# HPCC_Connector_A.net
KiCad netlist of a schematic drawn in Altium Designer
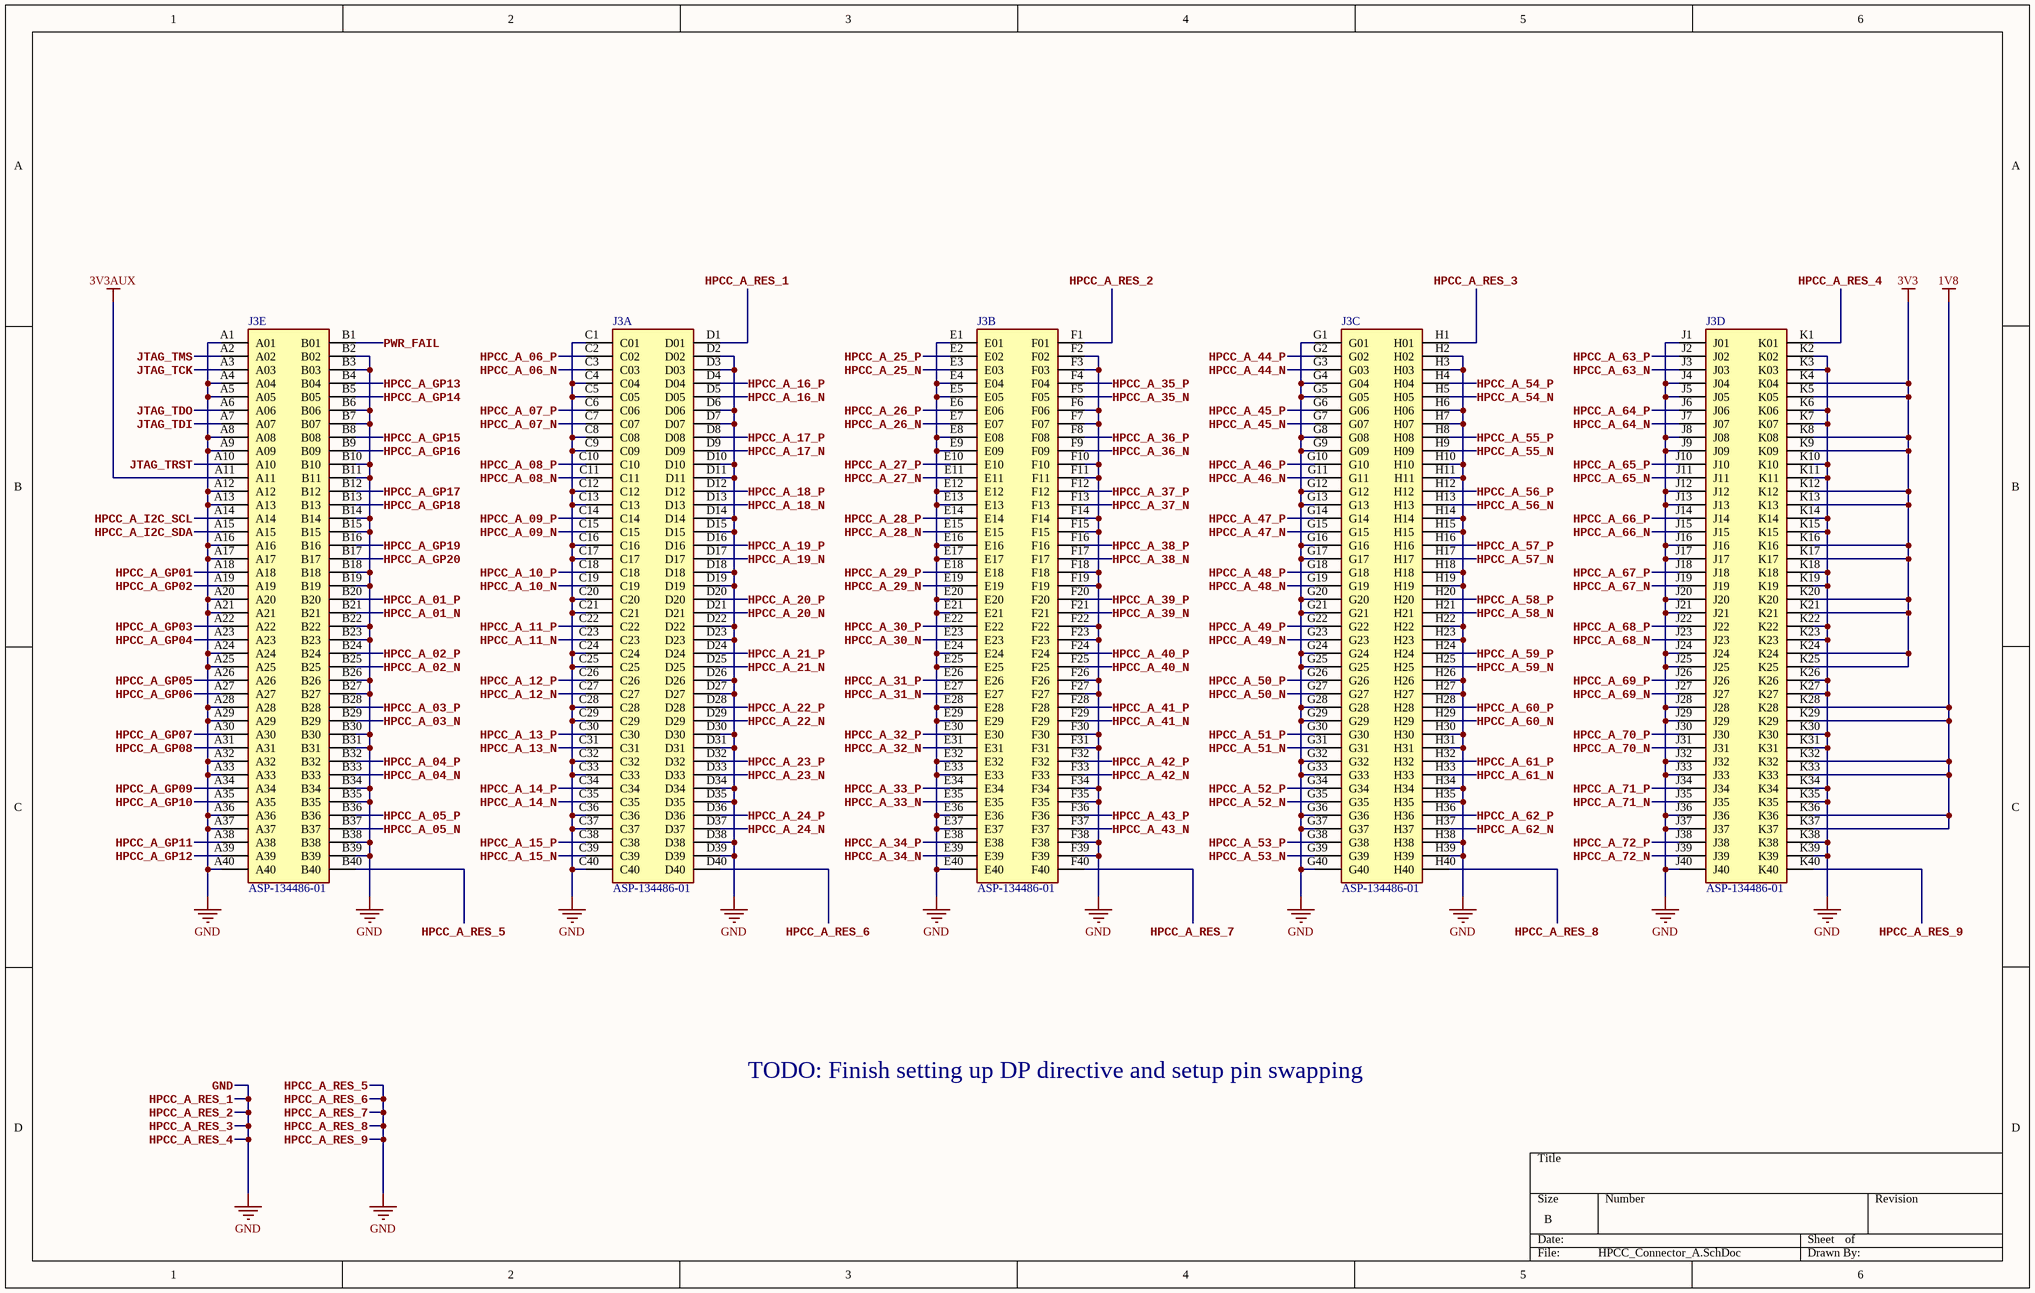
[diagram p0: HPCC_Connector_A.SchDoc]

(export (version "E")
  (design (tool "Eeschema 10.0.6"))
  (components
    (comp (ref "J3")
      (value "ASP-134486-01")
      (footprint "SAMTEC_ASP-134486-01")
      (description "400 Position Connector Array, Female Sockets Surface Mount Gold")
      (fields (field (name "MANUFACTURER") "Samtec"))
      (libsource (lib "Capstone_Schematic_Library") (part "ASP-134486-01"))
    )
  )
  (nets
    (net (code "1") (name "/HPCC_A_01_N") (class "Default")
      (node (ref "J3") (pin "B21") (pinfunction "B21_B21") (pintype "passive"))
    )
    (net (code "2") (name "/HPCC_A_01_P") (class "Default")
      (node (ref "J3") (pin "B20") (pinfunction "B20_B20") (pintype "passive"))
    )
    (net (code "3") (name "/HPCC_A_02_N") (class "Default")
      (node (ref "J3") (pin "B25") (pinfunction "B25_B25") (pintype "passive"))
    )
    (net (code "4") (name "/HPCC_A_02_P") (class "Default")
      (node (ref "J3") (pin "B24") (pinfunction "B24_B24") (pintype "passive"))
    )
    (net (code "5") (name "/HPCC_A_03_N") (class "Default")
      (node (ref "J3") (pin "B29") (pinfunction "B29_B29") (pintype "passive"))
    )
    (net (code "6") (name "/HPCC_A_03_P") (class "Default")
      (node (ref "J3") (pin "B28") (pinfunction "B28_B28") (pintype "passive"))
    )
    (net (code "7") (name "/HPCC_A_04_N") (class "Default")
      (node (ref "J3") (pin "B33") (pinfunction "B33_B33") (pintype "passive"))
    )
    (net (code "8") (name "/HPCC_A_04_P") (class "Default")
      (node (ref "J3") (pin "B32") (pinfunction "B32_B32") (pintype "passive"))
    )
    (net (code "9") (name "/HPCC_A_05_N") (class "Default")
      (node (ref "J3") (pin "B37") (pinfunction "B37_B37") (pintype "passive"))
    )
    (net (code "10") (name "/HPCC_A_05_P") (class "Default")
      (node (ref "J3") (pin "B36") (pinfunction "B36_B36") (pintype "passive"))
    )
    (net (code "11") (name "/HPCC_A_06_N") (class "Default")
      (node (ref "J3") (pin "C3") (pinfunction "C03_C3") (pintype "passive"))
    )
    (net (code "12") (name "/HPCC_A_06_P") (class "Default")
      (node (ref "J3") (pin "C2") (pinfunction "C02_C2") (pintype "passive"))
    )
    (net (code "13") (name "/HPCC_A_07_N") (class "Default")
      (node (ref "J3") (pin "C7") (pinfunction "C07_C7") (pintype "passive"))
    )
    (net (code "14") (name "/HPCC_A_07_P") (class "Default")
      (node (ref "J3") (pin "C6") (pinfunction "C06_C6") (pintype "passive"))
    )
    (net (code "15") (name "/HPCC_A_08_N") (class "Default")
      (node (ref "J3") (pin "C11") (pinfunction "C11_C11") (pintype "passive"))
    )
    (net (code "16") (name "/HPCC_A_08_P") (class "Default")
      (node (ref "J3") (pin "C10") (pinfunction "C10_C10") (pintype "passive"))
    )
    (net (code "17") (name "/HPCC_A_09_N") (class "Default")
      (node (ref "J3") (pin "C15") (pinfunction "C15_C15") (pintype "passive"))
    )
    (net (code "18") (name "/HPCC_A_09_P") (class "Default")
      (node (ref "J3") (pin "C14") (pinfunction "C14_C14") (pintype "passive"))
    )
    (net (code "19") (name "/HPCC_A_10_N") (class "Default")
      (node (ref "J3") (pin "C19") (pinfunction "C19_C19") (pintype "passive"))
    )
    (net (code "20") (name "/HPCC_A_10_P") (class "Default")
      (node (ref "J3") (pin "C18") (pinfunction "C18_C18") (pintype "passive"))
    )
    (net (code "21") (name "/HPCC_A_11_N") (class "Default")
      (node (ref "J3") (pin "C23") (pinfunction "C23_C23") (pintype "passive"))
    )
    (net (code "22") (name "/HPCC_A_11_P") (class "Default")
      (node (ref "J3") (pin "C22") (pinfunction "C22_C22") (pintype "passive"))
    )
    (net (code "23") (name "/HPCC_A_12_N") (class "Default")
      (node (ref "J3") (pin "C27") (pinfunction "C27_C27") (pintype "passive"))
    )
    (net (code "24") (name "/HPCC_A_12_P") (class "Default")
      (node (ref "J3") (pin "C26") (pinfunction "C26_C26") (pintype "passive"))
    )
    (net (code "25") (name "/HPCC_A_13_N") (class "Default")
      (node (ref "J3") (pin "C31") (pinfunction "C31_C31") (pintype "passive"))
    )
    (net (code "26") (name "/HPCC_A_13_P") (class "Default")
      (node (ref "J3") (pin "C30") (pinfunction "C30_C30") (pintype "passive"))
    )
    (net (code "27") (name "/HPCC_A_14_N") (class "Default")
      (node (ref "J3") (pin "C35") (pinfunction "C35_C35") (pintype "passive"))
    )
    (net (code "28") (name "/HPCC_A_14_P") (class "Default")
      (node (ref "J3") (pin "C34") (pinfunction "C34_C34") (pintype "passive"))
    )
    (net (code "29") (name "/HPCC_A_15_N") (class "Default")
      (node (ref "J3") (pin "C39") (pinfunction "C39_C39") (pintype "passive"))
    )
    (net (code "30") (name "/HPCC_A_15_P") (class "Default")
      (node (ref "J3") (pin "C38") (pinfunction "C38_C38") (pintype "passive"))
    )
    (net (code "31") (name "/HPCC_A_16_N") (class "Default")
      (node (ref "J3") (pin "D5") (pinfunction "D05_D5") (pintype "passive"))
    )
    (net (code "32") (name "/HPCC_A_16_P") (class "Default")
      (node (ref "J3") (pin "D4") (pinfunction "D04_D4") (pintype "passive"))
    )
    (net (code "33") (name "/HPCC_A_17_N") (class "Default")
      (node (ref "J3") (pin "D9") (pinfunction "D09_D9") (pintype "passive"))
    )
    (net (code "34") (name "/HPCC_A_17_P") (class "Default")
      (node (ref "J3") (pin "D8") (pinfunction "D08_D8") (pintype "passive"))
    )
    (net (code "35") (name "/HPCC_A_18_N") (class "Default")
      (node (ref "J3") (pin "D13") (pinfunction "D13_D13") (pintype "passive"))
    )
    (net (code "36") (name "/HPCC_A_18_P") (class "Default")
      (node (ref "J3") (pin "D12") (pinfunction "D12_D12") (pintype "passive"))
    )
    (net (code "37") (name "/HPCC_A_19_N") (class "Default")
      (node (ref "J3") (pin "D17") (pinfunction "D17_D17") (pintype "passive"))
    )
    (net (code "38") (name "/HPCC_A_19_P") (class "Default")
      (node (ref "J3") (pin "D16") (pinfunction "D16_D16") (pintype "passive"))
    )
    (net (code "39") (name "/HPCC_A_20_N") (class "Default")
      (node (ref "J3") (pin "D21") (pinfunction "D21_D21") (pintype "passive"))
    )
    (net (code "40") (name "/HPCC_A_20_P") (class "Default")
      (node (ref "J3") (pin "D20") (pinfunction "D20_D20") (pintype "passive"))
    )
    (net (code "41") (name "/HPCC_A_21_N") (class "Default")
      (node (ref "J3") (pin "D25") (pinfunction "D25_D25") (pintype "passive"))
    )
    (net (code "42") (name "/HPCC_A_21_P") (class "Default")
      (node (ref "J3") (pin "D24") (pinfunction "D24_D24") (pintype "passive"))
    )
    (net (code "43") (name "/HPCC_A_22_N") (class "Default")
      (node (ref "J3") (pin "D29") (pinfunction "D29_D29") (pintype "passive"))
    )
    (net (code "44") (name "/HPCC_A_22_P") (class "Default")
      (node (ref "J3") (pin "D28") (pinfunction "D28_D28") (pintype "passive"))
    )
    (net (code "45") (name "/HPCC_A_23_N") (class "Default")
      (node (ref "J3") (pin "D33") (pinfunction "D33_D33") (pintype "passive"))
    )
    (net (code "46") (name "/HPCC_A_23_P") (class "Default")
      (node (ref "J3") (pin "D32") (pinfunction "D32_D32") (pintype "passive"))
    )
    (net (code "47") (name "/HPCC_A_24_N") (class "Default")
      (node (ref "J3") (pin "D37") (pinfunction "D37_D37") (pintype "passive"))
    )
    (net (code "48") (name "/HPCC_A_24_P") (class "Default")
      (node (ref "J3") (pin "D36") (pinfunction "D36_D36") (pintype "passive"))
    )
    (net (code "49") (name "/HPCC_A_25_N") (class "Default")
      (node (ref "J3") (pin "E3") (pinfunction "E03_E3") (pintype "passive"))
    )
    (net (code "50") (name "/HPCC_A_25_P") (class "Default")
      (node (ref "J3") (pin "E2") (pinfunction "E02_E2") (pintype "passive"))
    )
    (net (code "51") (name "/HPCC_A_26_N") (class "Default")
      (node (ref "J3") (pin "E7") (pinfunction "E07_E7") (pintype "passive"))
    )
    (net (code "52") (name "/HPCC_A_26_P") (class "Default")
      (node (ref "J3") (pin "E6") (pinfunction "E06_E6") (pintype "passive"))
    )
    (net (code "53") (name "/HPCC_A_27_N") (class "Default")
      (node (ref "J3") (pin "E11") (pinfunction "E11_E11") (pintype "passive"))
    )
    (net (code "54") (name "/HPCC_A_27_P") (class "Default")
      (node (ref "J3") (pin "E10") (pinfunction "E10_E10") (pintype "passive"))
    )
    (net (code "55") (name "/HPCC_A_28_N") (class "Default")
      (node (ref "J3") (pin "E15") (pinfunction "E15_E15") (pintype "passive"))
    )
    (net (code "56") (name "/HPCC_A_28_P") (class "Default")
      (node (ref "J3") (pin "E14") (pinfunction "E14_E14") (pintype "passive"))
    )
    (net (code "57") (name "/HPCC_A_29_N") (class "Default")
      (node (ref "J3") (pin "E19") (pinfunction "E19_E19") (pintype "passive"))
    )
    (net (code "58") (name "/HPCC_A_29_P") (class "Default")
      (node (ref "J3") (pin "E18") (pinfunction "E18_E18") (pintype "passive"))
    )
    (net (code "59") (name "/HPCC_A_30_N") (class "Default")
      (node (ref "J3") (pin "E23") (pinfunction "E23_E23") (pintype "passive"))
    )
    (net (code "60") (name "/HPCC_A_30_P") (class "Default")
      (node (ref "J3") (pin "E22") (pinfunction "E22_E22") (pintype "passive"))
    )
    (net (code "61") (name "/HPCC_A_31_N") (class "Default")
      (node (ref "J3") (pin "E27") (pinfunction "E27_E27") (pintype "passive"))
    )
    (net (code "62") (name "/HPCC_A_31_P") (class "Default")
      (node (ref "J3") (pin "E26") (pinfunction "E26_E26") (pintype "passive"))
    )
    (net (code "63") (name "/HPCC_A_32_N") (class "Default")
      (node (ref "J3") (pin "E31") (pinfunction "E31_E31") (pintype "passive"))
    )
    (net (code "64") (name "/HPCC_A_32_P") (class "Default")
      (node (ref "J3") (pin "E30") (pinfunction "E30_E30") (pintype "passive"))
    )
    (net (code "65") (name "/HPCC_A_33_N") (class "Default")
      (node (ref "J3") (pin "E35") (pinfunction "E35_E35") (pintype "passive"))
    )
    (net (code "66") (name "/HPCC_A_33_P") (class "Default")
      (node (ref "J3") (pin "E34") (pinfunction "E34_E34") (pintype "passive"))
    )
    (net (code "67") (name "/HPCC_A_34_N") (class "Default")
      (node (ref "J3") (pin "E39") (pinfunction "E39_E39") (pintype "passive"))
    )
    (net (code "68") (name "/HPCC_A_34_P") (class "Default")
      (node (ref "J3") (pin "E38") (pinfunction "E38_E38") (pintype "passive"))
    )
    (net (code "69") (name "/HPCC_A_35_N") (class "Default")
      (node (ref "J3") (pin "F5") (pinfunction "F05_F5") (pintype "passive"))
    )
    (net (code "70") (name "/HPCC_A_35_P") (class "Default")
      (node (ref "J3") (pin "F4") (pinfunction "F04_F4") (pintype "passive"))
    )
    (net (code "71") (name "/HPCC_A_36_N") (class "Default")
      (node (ref "J3") (pin "F9") (pinfunction "F09_F9") (pintype "passive"))
    )
    (net (code "72") (name "/HPCC_A_36_P") (class "Default")
      (node (ref "J3") (pin "F8") (pinfunction "F08_F8") (pintype "passive"))
    )
    (net (code "73") (name "/HPCC_A_37_N") (class "Default")
      (node (ref "J3") (pin "F13") (pinfunction "F13_F13") (pintype "passive"))
    )
    (net (code "74") (name "/HPCC_A_37_P") (class "Default")
      (node (ref "J3") (pin "F12") (pinfunction "F12_F12") (pintype "passive"))
    )
    (net (code "75") (name "/HPCC_A_38_N") (class "Default")
      (node (ref "J3") (pin "F17") (pinfunction "F17_F17") (pintype "passive"))
    )
    (net (code "76") (name "/HPCC_A_38_P") (class "Default")
      (node (ref "J3") (pin "F16") (pinfunction "F16_F16") (pintype "passive"))
    )
    (net (code "77") (name "/HPCC_A_39_N") (class "Default")
      (node (ref "J3") (pin "F21") (pinfunction "F21_F21") (pintype "passive"))
    )
    (net (code "78") (name "/HPCC_A_39_P") (class "Default")
      (node (ref "J3") (pin "F20") (pinfunction "F20_F20") (pintype "passive"))
    )
    (net (code "79") (name "/HPCC_A_40_N") (class "Default")
      (node (ref "J3") (pin "F25") (pinfunction "F25_F25") (pintype "passive"))
    )
    (net (code "80") (name "/HPCC_A_40_P") (class "Default")
      (node (ref "J3") (pin "F24") (pinfunction "F24_F24") (pintype "passive"))
    )
    (net (code "81") (name "/HPCC_A_41_N") (class "Default")
      (node (ref "J3") (pin "F29") (pinfunction "F29_F29") (pintype "passive"))
    )
    (net (code "82") (name "/HPCC_A_41_P") (class "Default")
      (node (ref "J3") (pin "F28") (pinfunction "F28_F28") (pintype "passive"))
    )
    (net (code "83") (name "/HPCC_A_42_N") (class "Default")
      (node (ref "J3") (pin "F33") (pinfunction "F33_F33") (pintype "passive"))
    )
    (net (code "84") (name "/HPCC_A_42_P") (class "Default")
      (node (ref "J3") (pin "F32") (pinfunction "F32_F32") (pintype "passive"))
    )
    (net (code "85") (name "/HPCC_A_43_N") (class "Default")
      (node (ref "J3") (pin "F37") (pinfunction "F37_F37") (pintype "passive"))
    )
    (net (code "86") (name "/HPCC_A_43_P") (class "Default")
      (node (ref "J3") (pin "F36") (pinfunction "F36_F36") (pintype "passive"))
    )
    (net (code "87") (name "/HPCC_A_44_N") (class "Default")
      (node (ref "J3") (pin "G3") (pinfunction "G03_G3") (pintype "passive"))
    )
    (net (code "88") (name "/HPCC_A_44_P") (class "Default")
      (node (ref "J3") (pin "G2") (pinfunction "G02_G2") (pintype "passive"))
    )
    (net (code "89") (name "/HPCC_A_45_N") (class "Default")
      (node (ref "J3") (pin "G7") (pinfunction "G07_G7") (pintype "passive"))
    )
    (net (code "90") (name "/HPCC_A_45_P") (class "Default")
      (node (ref "J3") (pin "G6") (pinfunction "G06_G6") (pintype "passive"))
    )
    (net (code "91") (name "/HPCC_A_46_N") (class "Default")
      (node (ref "J3") (pin "G11") (pinfunction "G11_G11") (pintype "passive"))
    )
    (net (code "92") (name "/HPCC_A_46_P") (class "Default")
      (node (ref "J3") (pin "G10") (pinfunction "G10_G10") (pintype "passive"))
    )
    (net (code "93") (name "/HPCC_A_47_N") (class "Default")
      (node (ref "J3") (pin "G15") (pinfunction "G15_G15") (pintype "passive"))
    )
    (net (code "94") (name "/HPCC_A_47_P") (class "Default")
      (node (ref "J3") (pin "G14") (pinfunction "G14_G14") (pintype "passive"))
    )
    (net (code "95") (name "/HPCC_A_48_N") (class "Default")
      (node (ref "J3") (pin "G19") (pinfunction "G19_G19") (pintype "passive"))
    )
    (net (code "96") (name "/HPCC_A_48_P") (class "Default")
      (node (ref "J3") (pin "G18") (pinfunction "G18_G18") (pintype "passive"))
    )
    (net (code "97") (name "/HPCC_A_49_N") (class "Default")
      (node (ref "J3") (pin "G23") (pinfunction "G23_G23") (pintype "passive"))
    )
    (net (code "98") (name "/HPCC_A_49_P") (class "Default")
      (node (ref "J3") (pin "G22") (pinfunction "G22_G22") (pintype "passive"))
    )
    (net (code "99") (name "/HPCC_A_50_N") (class "Default")
      (node (ref "J3") (pin "G27") (pinfunction "G27_G27") (pintype "passive"))
    )
    (net (code "100") (name "/HPCC_A_50_P") (class "Default")
      (node (ref "J3") (pin "G26") (pinfunction "G26_G26") (pintype "passive"))
    )
    (net (code "101") (name "/HPCC_A_51_N") (class "Default")
      (node (ref "J3") (pin "G31") (pinfunction "G31_G31") (pintype "passive"))
    )
    (net (code "102") (name "/HPCC_A_51_P") (class "Default")
      (node (ref "J3") (pin "G30") (pinfunction "G30_G30") (pintype "passive"))
    )
    (net (code "103") (name "/HPCC_A_52_N") (class "Default")
      (node (ref "J3") (pin "G35") (pinfunction "G35_G35") (pintype "passive"))
    )
    (net (code "104") (name "/HPCC_A_52_P") (class "Default")
      (node (ref "J3") (pin "G34") (pinfunction "G34_G34") (pintype "passive"))
    )
    (net (code "105") (name "/HPCC_A_53_N") (class "Default")
      (node (ref "J3") (pin "G39") (pinfunction "G39_G39") (pintype "passive"))
    )
    (net (code "106") (name "/HPCC_A_53_P") (class "Default")
      (node (ref "J3") (pin "G38") (pinfunction "G38_G38") (pintype "passive"))
    )
    (net (code "107") (name "/HPCC_A_54_N") (class "Default")
      (node (ref "J3") (pin "H5") (pinfunction "H05_H5") (pintype "passive"))
    )
    (net (code "108") (name "/HPCC_A_54_P") (class "Default")
      (node (ref "J3") (pin "H4") (pinfunction "H04_H4") (pintype "passive"))
    )
    (net (code "109") (name "/HPCC_A_55_N") (class "Default")
      (node (ref "J3") (pin "H9") (pinfunction "H09_H9") (pintype "passive"))
    )
    (net (code "110") (name "/HPCC_A_55_P") (class "Default")
      (node (ref "J3") (pin "H8") (pinfunction "H08_H8") (pintype "passive"))
    )
    (net (code "111") (name "/HPCC_A_56_N") (class "Default")
      (node (ref "J3") (pin "H13") (pinfunction "H13_H13") (pintype "passive"))
    )
    (net (code "112") (name "/HPCC_A_56_P") (class "Default")
      (node (ref "J3") (pin "H12") (pinfunction "H12_H12") (pintype "passive"))
    )
    (net (code "113") (name "/HPCC_A_57_N") (class "Default")
      (node (ref "J3") (pin "H17") (pinfunction "H17_H17") (pintype "passive"))
    )
    (net (code "114") (name "/HPCC_A_57_P") (class "Default")
      (node (ref "J3") (pin "H16") (pinfunction "H16_H16") (pintype "passive"))
    )
    (net (code "115") (name "/HPCC_A_58_N") (class "Default")
      (node (ref "J3") (pin "H21") (pinfunction "H21_H21") (pintype "passive"))
    )
    (net (code "116") (name "/HPCC_A_58_P") (class "Default")
      (node (ref "J3") (pin "H20") (pinfunction "H20_H20") (pintype "passive"))
    )
    (net (code "117") (name "/HPCC_A_59_N") (class "Default")
      (node (ref "J3") (pin "H25") (pinfunction "H25_H25") (pintype "passive"))
    )
    (net (code "118") (name "/HPCC_A_59_P") (class "Default")
      (node (ref "J3") (pin "H24") (pinfunction "H24_H24") (pintype "passive"))
    )
    (net (code "119") (name "/HPCC_A_60_N") (class "Default")
      (node (ref "J3") (pin "H29") (pinfunction "H29_H29") (pintype "passive"))
    )
    (net (code "120") (name "/HPCC_A_60_P") (class "Default")
      (node (ref "J3") (pin "H28") (pinfunction "H28_H28") (pintype "passive"))
    )
    (net (code "121") (name "/HPCC_A_61_N") (class "Default")
      (node (ref "J3") (pin "H33") (pinfunction "H33_H33") (pintype "passive"))
    )
    (net (code "122") (name "/HPCC_A_61_P") (class "Default")
      (node (ref "J3") (pin "H32") (pinfunction "H32_H32") (pintype "passive"))
    )
    (net (code "123") (name "/HPCC_A_62_N") (class "Default")
      (node (ref "J3") (pin "H37") (pinfunction "H37_H37") (pintype "passive"))
    )
    (net (code "124") (name "/HPCC_A_62_P") (class "Default")
      (node (ref "J3") (pin "H36") (pinfunction "H36_H36") (pintype "passive"))
    )
    (net (code "125") (name "/HPCC_A_63_N") (class "Default")
      (node (ref "J3") (pin "J3") (pinfunction "J03_J3") (pintype "passive"))
    )
    (net (code "126") (name "/HPCC_A_63_P") (class "Default")
      (node (ref "J3") (pin "J2") (pinfunction "J02_J2") (pintype "passive"))
    )
    (net (code "127") (name "/HPCC_A_64_N") (class "Default")
      (node (ref "J3") (pin "J7") (pinfunction "J07_J7") (pintype "passive"))
    )
    (net (code "128") (name "/HPCC_A_64_P") (class "Default")
      (node (ref "J3") (pin "J6") (pinfunction "J06_J6") (pintype "passive"))
    )
    (net (code "129") (name "/HPCC_A_65_N") (class "Default")
      (node (ref "J3") (pin "J11") (pinfunction "J11_J11") (pintype "passive"))
    )
    (net (code "130") (name "/HPCC_A_65_P") (class "Default")
      (node (ref "J3") (pin "J10") (pinfunction "J10_J10") (pintype "passive"))
    )
    (net (code "131") (name "/HPCC_A_66_N") (class "Default")
      (node (ref "J3") (pin "J15") (pinfunction "J15_J15") (pintype "passive"))
    )
    (net (code "132") (name "/HPCC_A_66_P") (class "Default")
      (node (ref "J3") (pin "J14") (pinfunction "J14_J14") (pintype "passive"))
    )
    (net (code "133") (name "/HPCC_A_67_N") (class "Default")
      (node (ref "J3") (pin "J19") (pinfunction "J19_J19") (pintype "passive"))
    )
    (net (code "134") (name "/HPCC_A_67_P") (class "Default")
      (node (ref "J3") (pin "J18") (pinfunction "J18_J18") (pintype "passive"))
    )
    (net (code "135") (name "/HPCC_A_68_N") (class "Default")
      (node (ref "J3") (pin "J23") (pinfunction "J23_J23") (pintype "passive"))
    )
    (net (code "136") (name "/HPCC_A_68_P") (class "Default")
      (node (ref "J3") (pin "J22") (pinfunction "J22_J22") (pintype "passive"))
    )
    (net (code "137") (name "/HPCC_A_69_N") (class "Default")
      (node (ref "J3") (pin "J27") (pinfunction "J27_J27") (pintype "passive"))
    )
    (net (code "138") (name "/HPCC_A_69_P") (class "Default")
      (node (ref "J3") (pin "J26") (pinfunction "J26_J26") (pintype "passive"))
    )
    (net (code "139") (name "/HPCC_A_70_N") (class "Default")
      (node (ref "J3") (pin "J31") (pinfunction "J31_J31") (pintype "passive"))
    )
    (net (code "140") (name "/HPCC_A_70_P") (class "Default")
      (node (ref "J3") (pin "J30") (pinfunction "J30_J30") (pintype "passive"))
    )
    (net (code "141") (name "/HPCC_A_71_N") (class "Default")
      (node (ref "J3") (pin "J35") (pinfunction "J35_J35") (pintype "passive"))
    )
    (net (code "142") (name "/HPCC_A_71_P") (class "Default")
      (node (ref "J3") (pin "J34") (pinfunction "J34_J34") (pintype "passive"))
    )
    (net (code "143") (name "/HPCC_A_72_N") (class "Default")
      (node (ref "J3") (pin "J39") (pinfunction "J39_J39") (pintype "passive"))
    )
    (net (code "144") (name "/HPCC_A_72_P") (class "Default")
      (node (ref "J3") (pin "J38") (pinfunction "J38_J38") (pintype "passive"))
    )
    (net (code "145") (name "/HPCC_A_GP01") (class "Default")
      (node (ref "J3") (pin "A18") (pinfunction "A18_A18") (pintype "passive"))
    )
    (net (code "146") (name "/HPCC_A_GP02") (class "Default")
      (node (ref "J3") (pin "A19") (pinfunction "A19_A19") (pintype "passive"))
    )
    (net (code "147") (name "/HPCC_A_GP03") (class "Default")
      (node (ref "J3") (pin "A22") (pinfunction "A22_A22") (pintype "passive"))
    )
    (net (code "148") (name "/HPCC_A_GP04") (class "Default")
      (node (ref "J3") (pin "A23") (pinfunction "A23_A23") (pintype "passive"))
    )
    (net (code "149") (name "/HPCC_A_GP05") (class "Default")
      (node (ref "J3") (pin "A26") (pinfunction "A26_A26") (pintype "passive"))
    )
    (net (code "150") (name "/HPCC_A_GP06") (class "Default")
      (node (ref "J3") (pin "A27") (pinfunction "A27_A27") (pintype "passive"))
    )
    (net (code "151") (name "/HPCC_A_GP07") (class "Default")
      (node (ref "J3") (pin "A30") (pinfunction "A30_A30") (pintype "passive"))
    )
    (net (code "152") (name "/HPCC_A_GP08") (class "Default")
      (node (ref "J3") (pin "A31") (pinfunction "A31_A31") (pintype "passive"))
    )
    (net (code "153") (name "/HPCC_A_GP09") (class "Default")
      (node (ref "J3") (pin "A34") (pinfunction "A34_A34") (pintype "passive"))
    )
    (net (code "154") (name "/HPCC_A_GP10") (class "Default")
      (node (ref "J3") (pin "A35") (pinfunction "A35_A35") (pintype "passive"))
    )
    (net (code "155") (name "/HPCC_A_GP11") (class "Default")
      (node (ref "J3") (pin "A38") (pinfunction "A38_A38") (pintype "passive"))
    )
    (net (code "156") (name "/HPCC_A_GP12") (class "Default")
      (node (ref "J3") (pin "A39") (pinfunction "A39_A39") (pintype "passive"))
    )
    (net (code "157") (name "/HPCC_A_GP13") (class "Default")
      (node (ref "J3") (pin "B4") (pinfunction "B04_B4") (pintype "passive"))
    )
    (net (code "158") (name "/HPCC_A_GP14") (class "Default")
      (node (ref "J3") (pin "B5") (pinfunction "B05_B5") (pintype "passive"))
    )
    (net (code "159") (name "/HPCC_A_GP15") (class "Default")
      (node (ref "J3") (pin "B8") (pinfunction "B08_B8") (pintype "passive"))
    )
    (net (code "160") (name "/HPCC_A_GP16") (class "Default")
      (node (ref "J3") (pin "B9") (pinfunction "B09_B9") (pintype "passive"))
    )
    (net (code "161") (name "/HPCC_A_GP17") (class "Default")
      (node (ref "J3") (pin "B12") (pinfunction "B12_B12") (pintype "passive"))
    )
    (net (code "162") (name "/HPCC_A_GP18") (class "Default")
      (node (ref "J3") (pin "B13") (pinfunction "B13_B13") (pintype "passive"))
    )
    (net (code "163") (name "/HPCC_A_GP19") (class "Default")
      (node (ref "J3") (pin "B16") (pinfunction "B16_B16") (pintype "passive"))
    )
    (net (code "164") (name "/HPCC_A_GP20") (class "Default")
      (node (ref "J3") (pin "B17") (pinfunction "B17_B17") (pintype "passive"))
    )
    (net (code "165") (name "/HPCC_A_I2C_SCL") (class "Default")
      (node (ref "J3") (pin "A14") (pinfunction "A14_A14") (pintype "passive"))
    )
    (net (code "166") (name "/HPCC_A_I2C_SDA") (class "Default")
      (node (ref "J3") (pin "A15") (pinfunction "A15_A15") (pintype "passive"))
    )
    (net (code "167") (name "/JTAG_TCK") (class "Default")
      (node (ref "J3") (pin "A3") (pinfunction "A03_A3") (pintype "passive"))
    )
    (net (code "168") (name "/JTAG_TDI") (class "Default")
      (node (ref "J3") (pin "A7") (pinfunction "A07_A7") (pintype "passive"))
    )
    (net (code "169") (name "/JTAG_TDO") (class "Default")
      (node (ref "J3") (pin "A6") (pinfunction "A06_A6") (pintype "passive"))
    )
    (net (code "170") (name "/JTAG_TMS") (class "Default")
      (node (ref "J3") (pin "A2") (pinfunction "A02_A2") (pintype "passive"))
    )
    (net (code "171") (name "/JTAG_TRST") (class "Default")
      (node (ref "J3") (pin "A10") (pinfunction "A10_A10") (pintype "passive"))
    )
    (net (code "172") (name "/PWR_FAIL") (class "Default")
      (node (ref "J3") (pin "B1") (pinfunction "B01_B1") (pintype "passive"))
    )
    (net (code "173") (name "1V8") (class "Default")
      (node (ref "J3") (pin "K28") (pinfunction "K28_K28") (pintype "passive"))
      (node (ref "J3") (pin "K29") (pinfunction "K29_K29") (pintype "passive"))
      (node (ref "J3") (pin "K32") (pinfunction "K32_K32") (pintype "passive"))
      (node (ref "J3") (pin "K33") (pinfunction "K33_K33") (pintype "passive"))
      (node (ref "J3") (pin "K36") (pinfunction "K36_K36") (pintype "passive"))
      (node (ref "J3") (pin "K37") (pinfunction "K37_K37") (pintype "passive"))
    )
    (net (code "174") (name "3V3") (class "Default")
      (node (ref "J3") (pin "K12") (pinfunction "K12_K12") (pintype "passive"))
      (node (ref "J3") (pin "K13") (pinfunction "K13_K13") (pintype "passive"))
      (node (ref "J3") (pin "K16") (pinfunction "K16_K16") (pintype "passive"))
      (node (ref "J3") (pin "K17") (pinfunction "K17_K17") (pintype "passive"))
      (node (ref "J3") (pin "K20") (pinfunction "K20_K20") (pintype "passive"))
      (node (ref "J3") (pin "K21") (pinfunction "K21_K21") (pintype "passive"))
      (node (ref "J3") (pin "K24") (pinfunction "K24_K24") (pintype "passive"))
      (node (ref "J3") (pin "K25") (pinfunction "K25_K25") (pintype "passive"))
      (node (ref "J3") (pin "K4") (pinfunction "K04_K4") (pintype "passive"))
      (node (ref "J3") (pin "K5") (pinfunction "K05_K5") (pintype "passive"))
      (node (ref "J3") (pin "K8") (pinfunction "K08_K8") (pintype "passive"))
      (node (ref "J3") (pin "K9") (pinfunction "K09_K9") (pintype "passive"))
    )
    (net (code "175") (name "3V3AUX") (class "Default")
      (node (ref "J3") (pin "A11") (pinfunction "A11_A11") (pintype "passive"))
    )
    (net (code "176") (name "GND") (class "Default")
      (node (ref "J3") (pin "A1") (pinfunction "A01_A1") (pintype "passive"))
      (node (ref "J3") (pin "A12") (pinfunction "A12_A12") (pintype "passive"))
      (node (ref "J3") (pin "A13") (pinfunction "A13_A13") (pintype "passive"))
      (node (ref "J3") (pin "A16") (pinfunction "A16_A16") (pintype "passive"))
      (node (ref "J3") (pin "A17") (pinfunction "A17_A17") (pintype "passive"))
      (node (ref "J3") (pin "A20") (pinfunction "A20_A20") (pintype "passive"))
      (node (ref "J3") (pin "A21") (pinfunction "A21_A21") (pintype "passive"))
      (node (ref "J3") (pin "A24") (pinfunction "A24_A24") (pintype "passive"))
      (node (ref "J3") (pin "A25") (pinfunction "A25_A25") (pintype "passive"))
      (node (ref "J3") (pin "A28") (pinfunction "A28_A28") (pintype "passive"))
      (node (ref "J3") (pin "A29") (pinfunction "A29_A29") (pintype "passive"))
      (node (ref "J3") (pin "A32") (pinfunction "A32_A32") (pintype "passive"))
      (node (ref "J3") (pin "A33") (pinfunction "A33_A33") (pintype "passive"))
      (node (ref "J3") (pin "A36") (pinfunction "A36_A36") (pintype "passive"))
      (node (ref "J3") (pin "A37") (pinfunction "A37_A37") (pintype "passive"))
      (node (ref "J3") (pin "A4") (pinfunction "A04_A4") (pintype "passive"))
      (node (ref "J3") (pin "A40") (pinfunction "A40_A40") (pintype "passive"))
      (node (ref "J3") (pin "A5") (pinfunction "A05_A5") (pintype "passive"))
      (node (ref "J3") (pin "A8") (pinfunction "A08_A8") (pintype "passive"))
      (node (ref "J3") (pin "A9") (pinfunction "A09_A9") (pintype "passive"))
      (node (ref "J3") (pin "B10") (pinfunction "B10_B10") (pintype "passive"))
      (node (ref "J3") (pin "B11") (pinfunction "B11_B11") (pintype "passive"))
      (node (ref "J3") (pin "B14") (pinfunction "B14_B14") (pintype "passive"))
      (node (ref "J3") (pin "B15") (pinfunction "B15_B15") (pintype "passive"))
      (node (ref "J3") (pin "B18") (pinfunction "B18_B18") (pintype "passive"))
      (node (ref "J3") (pin "B19") (pinfunction "B19_B19") (pintype "passive"))
      (node (ref "J3") (pin "B2") (pinfunction "B02_B2") (pintype "passive"))
      (node (ref "J3") (pin "B22") (pinfunction "B22_B22") (pintype "passive"))
      (node (ref "J3") (pin "B23") (pinfunction "B23_B23") (pintype "passive"))
      (node (ref "J3") (pin "B26") (pinfunction "B26_B26") (pintype "passive"))
      (node (ref "J3") (pin "B27") (pinfunction "B27_B27") (pintype "passive"))
      (node (ref "J3") (pin "B3") (pinfunction "B03_B3") (pintype "passive"))
      (node (ref "J3") (pin "B30") (pinfunction "B30_B30") (pintype "passive"))
      (node (ref "J3") (pin "B31") (pinfunction "B31_B31") (pintype "passive"))
      (node (ref "J3") (pin "B34") (pinfunction "B34_B34") (pintype "passive"))
      (node (ref "J3") (pin "B35") (pinfunction "B35_B35") (pintype "passive"))
      (node (ref "J3") (pin "B38") (pinfunction "B38_B38") (pintype "passive"))
      (node (ref "J3") (pin "B39") (pinfunction "B39_B39") (pintype "passive"))
      (node (ref "J3") (pin "B40") (pinfunction "B40_B40") (pintype "passive"))
      (node (ref "J3") (pin "B6") (pinfunction "B06_B6") (pintype "passive"))
      (node (ref "J3") (pin "B7") (pinfunction "B07_B7") (pintype "passive"))
      (node (ref "J3") (pin "C1") (pinfunction "C01_C1") (pintype "passive"))
      (node (ref "J3") (pin "C12") (pinfunction "C12_C12") (pintype "passive"))
      (node (ref "J3") (pin "C13") (pinfunction "C13_C13") (pintype "passive"))
      (node (ref "J3") (pin "C16") (pinfunction "C16_C16") (pintype "passive"))
      (node (ref "J3") (pin "C17") (pinfunction "C17_C17") (pintype "passive"))
      (node (ref "J3") (pin "C20") (pinfunction "C20_C20") (pintype "passive"))
      (node (ref "J3") (pin "C21") (pinfunction "C21_C21") (pintype "passive"))
      (node (ref "J3") (pin "C24") (pinfunction "C24_C24") (pintype "passive"))
      (node (ref "J3") (pin "C25") (pinfunction "C25_C25") (pintype "passive"))
      (node (ref "J3") (pin "C28") (pinfunction "C28_C28") (pintype "passive"))
      (node (ref "J3") (pin "C29") (pinfunction "C29_C29") (pintype "passive"))
      (node (ref "J3") (pin "C32") (pinfunction "C32_C32") (pintype "passive"))
      (node (ref "J3") (pin "C33") (pinfunction "C33_C33") (pintype "passive"))
      (node (ref "J3") (pin "C36") (pinfunction "C36_C36") (pintype "passive"))
      (node (ref "J3") (pin "C37") (pinfunction "C37_C37") (pintype "passive"))
      (node (ref "J3") (pin "C4") (pinfunction "C04_C4") (pintype "passive"))
      (node (ref "J3") (pin "C40") (pinfunction "C40_C40") (pintype "passive"))
      (node (ref "J3") (pin "C5") (pinfunction "C05_C5") (pintype "passive"))
      (node (ref "J3") (pin "C8") (pinfunction "C08_C8") (pintype "passive"))
      (node (ref "J3") (pin "C9") (pinfunction "C09_C9") (pintype "passive"))
      (node (ref "J3") (pin "D1") (pinfunction "D01_D1") (pintype "passive"))
      (node (ref "J3") (pin "D10") (pinfunction "D10_D10") (pintype "passive"))
      (node (ref "J3") (pin "D11") (pinfunction "D11_D11") (pintype "passive"))
      (node (ref "J3") (pin "D14") (pinfunction "D14_D14") (pintype "passive"))
      (node (ref "J3") (pin "D15") (pinfunction "D15_D15") (pintype "passive"))
      (node (ref "J3") (pin "D18") (pinfunction "D18_D18") (pintype "passive"))
      (node (ref "J3") (pin "D19") (pinfunction "D19_D19") (pintype "passive"))
      (node (ref "J3") (pin "D2") (pinfunction "D02_D2") (pintype "passive"))
      (node (ref "J3") (pin "D22") (pinfunction "D22_D22") (pintype "passive"))
      (node (ref "J3") (pin "D23") (pinfunction "D23_D23") (pintype "passive"))
      (node (ref "J3") (pin "D26") (pinfunction "D26_D26") (pintype "passive"))
      (node (ref "J3") (pin "D27") (pinfunction "D27_D27") (pintype "passive"))
      (node (ref "J3") (pin "D3") (pinfunction "D03_D3") (pintype "passive"))
      (node (ref "J3") (pin "D30") (pinfunction "D30_D30") (pintype "passive"))
      (node (ref "J3") (pin "D31") (pinfunction "D31_D31") (pintype "passive"))
      (node (ref "J3") (pin "D34") (pinfunction "D34_D34") (pintype "passive"))
      (node (ref "J3") (pin "D35") (pinfunction "D35_D35") (pintype "passive"))
      (node (ref "J3") (pin "D38") (pinfunction "D38_D38") (pintype "passive"))
      (node (ref "J3") (pin "D39") (pinfunction "D39_D39") (pintype "passive"))
      (node (ref "J3") (pin "D40") (pinfunction "D40_D40") (pintype "passive"))
      (node (ref "J3") (pin "D6") (pinfunction "D06_D6") (pintype "passive"))
      (node (ref "J3") (pin "D7") (pinfunction "D07_D7") (pintype "passive"))
      (node (ref "J3") (pin "E1") (pinfunction "E01_E1") (pintype "passive"))
      (node (ref "J3") (pin "E12") (pinfunction "E12_E12") (pintype "passive"))
      (node (ref "J3") (pin "E13") (pinfunction "E13_E13") (pintype "passive"))
      (node (ref "J3") (pin "E16") (pinfunction "E16_E16") (pintype "passive"))
      (node (ref "J3") (pin "E17") (pinfunction "E17_E17") (pintype "passive"))
      (node (ref "J3") (pin "E20") (pinfunction "E20_E20") (pintype "passive"))
      (node (ref "J3") (pin "E21") (pinfunction "E21_E21") (pintype "passive"))
      (node (ref "J3") (pin "E24") (pinfunction "E24_E24") (pintype "passive"))
      (node (ref "J3") (pin "E25") (pinfunction "E25_E25") (pintype "passive"))
      (node (ref "J3") (pin "E28") (pinfunction "E28_E28") (pintype "passive"))
      (node (ref "J3") (pin "E29") (pinfunction "E29_E29") (pintype "passive"))
      (node (ref "J3") (pin "E32") (pinfunction "E32_E32") (pintype "passive"))
      (node (ref "J3") (pin "E33") (pinfunction "E33_E33") (pintype "passive"))
      (node (ref "J3") (pin "E36") (pinfunction "E36_E36") (pintype "passive"))
      (node (ref "J3") (pin "E37") (pinfunction "E37_E37") (pintype "passive"))
      (node (ref "J3") (pin "E4") (pinfunction "E04_E4") (pintype "passive"))
      (node (ref "J3") (pin "E40") (pinfunction "E40_E40") (pintype "passive"))
      (node (ref "J3") (pin "E5") (pinfunction "E05_E5") (pintype "passive"))
      (node (ref "J3") (pin "E8") (pinfunction "E08_E8") (pintype "passive"))
      (node (ref "J3") (pin "E9") (pinfunction "E09_E9") (pintype "passive"))
      (node (ref "J3") (pin "F1") (pinfunction "F01_F1") (pintype "passive"))
      (node (ref "J3") (pin "F10") (pinfunction "F10_F10") (pintype "passive"))
      (node (ref "J3") (pin "F11") (pinfunction "F11_F11") (pintype "passive"))
      (node (ref "J3") (pin "F14") (pinfunction "F14_F14") (pintype "passive"))
      (node (ref "J3") (pin "F15") (pinfunction "F15_F15") (pintype "passive"))
      (node (ref "J3") (pin "F18") (pinfunction "F18_F18") (pintype "passive"))
      (node (ref "J3") (pin "F19") (pinfunction "F19_F19") (pintype "passive"))
      (node (ref "J3") (pin "F2") (pinfunction "F02_F2") (pintype "passive"))
      (node (ref "J3") (pin "F22") (pinfunction "F22_F22") (pintype "passive"))
      (node (ref "J3") (pin "F23") (pinfunction "F23_F23") (pintype "passive"))
      (node (ref "J3") (pin "F26") (pinfunction "F26_F26") (pintype "passive"))
      (node (ref "J3") (pin "F27") (pinfunction "F27_F27") (pintype "passive"))
      (node (ref "J3") (pin "F3") (pinfunction "F03_F3") (pintype "passive"))
      (node (ref "J3") (pin "F30") (pinfunction "F30_F30") (pintype "passive"))
      (node (ref "J3") (pin "F31") (pinfunction "F31_F31") (pintype "passive"))
      (node (ref "J3") (pin "F34") (pinfunction "F34_F34") (pintype "passive"))
      (node (ref "J3") (pin "F35") (pinfunction "F35_F35") (pintype "passive"))
      (node (ref "J3") (pin "F38") (pinfunction "F38_F38") (pintype "passive"))
      (node (ref "J3") (pin "F39") (pinfunction "F39_F39") (pintype "passive"))
      (node (ref "J3") (pin "F40") (pinfunction "F40_F40") (pintype "passive"))
      (node (ref "J3") (pin "F6") (pinfunction "F06_F6") (pintype "passive"))
      (node (ref "J3") (pin "F7") (pinfunction "F07_F7") (pintype "passive"))
      (node (ref "J3") (pin "G1") (pinfunction "G01_G1") (pintype "passive"))
      (node (ref "J3") (pin "G12") (pinfunction "G12_G12") (pintype "passive"))
      (node (ref "J3") (pin "G13") (pinfunction "G13_G13") (pintype "passive"))
      (node (ref "J3") (pin "G16") (pinfunction "G16_G16") (pintype "passive"))
      (node (ref "J3") (pin "G17") (pinfunction "G17_G17") (pintype "passive"))
      (node (ref "J3") (pin "G20") (pinfunction "G20_G20") (pintype "passive"))
      (node (ref "J3") (pin "G21") (pinfunction "G21_G21") (pintype "passive"))
      (node (ref "J3") (pin "G24") (pinfunction "G24_G24") (pintype "passive"))
      (node (ref "J3") (pin "G25") (pinfunction "G25_G25") (pintype "passive"))
      (node (ref "J3") (pin "G28") (pinfunction "G28_G28") (pintype "passive"))
      (node (ref "J3") (pin "G29") (pinfunction "G29_G29") (pintype "passive"))
      (node (ref "J3") (pin "G32") (pinfunction "G32_G32") (pintype "passive"))
      (node (ref "J3") (pin "G33") (pinfunction "G33_G33") (pintype "passive"))
      (node (ref "J3") (pin "G36") (pinfunction "G36_G36") (pintype "passive"))
      (node (ref "J3") (pin "G37") (pinfunction "G37_G37") (pintype "passive"))
      (node (ref "J3") (pin "G4") (pinfunction "G04_G4") (pintype "passive"))
      (node (ref "J3") (pin "G40") (pinfunction "G40_G40") (pintype "passive"))
      (node (ref "J3") (pin "G5") (pinfunction "G05_G5") (pintype "passive"))
      (node (ref "J3") (pin "G8") (pinfunction "G08_G8") (pintype "passive"))
      (node (ref "J3") (pin "G9") (pinfunction "G09_G9") (pintype "passive"))
      (node (ref "J3") (pin "H1") (pinfunction "H01_H1") (pintype "passive"))
      (node (ref "J3") (pin "H10") (pinfunction "H10_H10") (pintype "passive"))
      (node (ref "J3") (pin "H11") (pinfunction "H11_H11") (pintype "passive"))
      (node (ref "J3") (pin "H14") (pinfunction "H14_H14") (pintype "passive"))
      (node (ref "J3") (pin "H15") (pinfunction "H15_H15") (pintype "passive"))
      (node (ref "J3") (pin "H18") (pinfunction "H18_H18") (pintype "passive"))
      (node (ref "J3") (pin "H19") (pinfunction "H19_H19") (pintype "passive"))
      (node (ref "J3") (pin "H2") (pinfunction "H02_H2") (pintype "passive"))
      (node (ref "J3") (pin "H22") (pinfunction "H22_H22") (pintype "passive"))
      (node (ref "J3") (pin "H23") (pinfunction "H23_H23") (pintype "passive"))
      (node (ref "J3") (pin "H26") (pinfunction "H26_H26") (pintype "passive"))
      (node (ref "J3") (pin "H27") (pinfunction "H27_H27") (pintype "passive"))
      (node (ref "J3") (pin "H3") (pinfunction "H03_H3") (pintype "passive"))
      (node (ref "J3") (pin "H30") (pinfunction "H30_H30") (pintype "passive"))
      (node (ref "J3") (pin "H31") (pinfunction "H31_H31") (pintype "passive"))
      (node (ref "J3") (pin "H34") (pinfunction "H34_H34") (pintype "passive"))
      (node (ref "J3") (pin "H35") (pinfunction "H35_H35") (pintype "passive"))
      (node (ref "J3") (pin "H38") (pinfunction "H38_H38") (pintype "passive"))
      (node (ref "J3") (pin "H39") (pinfunction "H39_H39") (pintype "passive"))
      (node (ref "J3") (pin "H40") (pinfunction "H40_H40") (pintype "passive"))
      (node (ref "J3") (pin "H6") (pinfunction "H06_H6") (pintype "passive"))
      (node (ref "J3") (pin "H7") (pinfunction "H07_H7") (pintype "passive"))
      (node (ref "J3") (pin "J1") (pinfunction "J01_J1") (pintype "passive"))
      (node (ref "J3") (pin "J12") (pinfunction "J12_J12") (pintype "passive"))
      (node (ref "J3") (pin "J13") (pinfunction "J13_J13") (pintype "passive"))
      (node (ref "J3") (pin "J16") (pinfunction "J16_J16") (pintype "passive"))
      (node (ref "J3") (pin "J17") (pinfunction "J17_J17") (pintype "passive"))
      (node (ref "J3") (pin "J20") (pinfunction "J20_J20") (pintype "passive"))
      (node (ref "J3") (pin "J21") (pinfunction "J21_J21") (pintype "passive"))
      (node (ref "J3") (pin "J24") (pinfunction "J24_J24") (pintype "passive"))
      (node (ref "J3") (pin "J25") (pinfunction "J25_J25") (pintype "passive"))
      (node (ref "J3") (pin "J28") (pinfunction "J28_J28") (pintype "passive"))
      (node (ref "J3") (pin "J29") (pinfunction "J29_J29") (pintype "passive"))
      (node (ref "J3") (pin "J32") (pinfunction "J32_J32") (pintype "passive"))
      (node (ref "J3") (pin "J33") (pinfunction "J33_J33") (pintype "passive"))
      (node (ref "J3") (pin "J36") (pinfunction "J36_J36") (pintype "passive"))
      (node (ref "J3") (pin "J37") (pinfunction "J37_J37") (pintype "passive"))
      (node (ref "J3") (pin "J4") (pinfunction "J04_J4") (pintype "passive"))
      (node (ref "J3") (pin "J40") (pinfunction "J40_J40") (pintype "passive"))
      (node (ref "J3") (pin "J5") (pinfunction "J05_J5") (pintype "passive"))
      (node (ref "J3") (pin "J8") (pinfunction "J08_J8") (pintype "passive"))
      (node (ref "J3") (pin "J9") (pinfunction "J09_J9") (pintype "passive"))
      (node (ref "J3") (pin "K1") (pinfunction "K01_K1") (pintype "passive"))
      (node (ref "J3") (pin "K10") (pinfunction "K10_K10") (pintype "passive"))
      (node (ref "J3") (pin "K11") (pinfunction "K11_K11") (pintype "passive"))
      (node (ref "J3") (pin "K14") (pinfunction "K14_K14") (pintype "passive"))
      (node (ref "J3") (pin "K15") (pinfunction "K15_K15") (pintype "passive"))
      (node (ref "J3") (pin "K18") (pinfunction "K18_K18") (pintype "passive"))
      (node (ref "J3") (pin "K19") (pinfunction "K19_K19") (pintype "passive"))
      (node (ref "J3") (pin "K2") (pinfunction "K02_K2") (pintype "passive"))
      (node (ref "J3") (pin "K22") (pinfunction "K22_K22") (pintype "passive"))
      (node (ref "J3") (pin "K23") (pinfunction "K23_K23") (pintype "passive"))
      (node (ref "J3") (pin "K26") (pinfunction "K26_K26") (pintype "passive"))
      (node (ref "J3") (pin "K27") (pinfunction "K27_K27") (pintype "passive"))
      (node (ref "J3") (pin "K3") (pinfunction "K03_K3") (pintype "passive"))
      (node (ref "J3") (pin "K30") (pinfunction "K30_K30") (pintype "passive"))
      (node (ref "J3") (pin "K31") (pinfunction "K31_K31") (pintype "passive"))
      (node (ref "J3") (pin "K34") (pinfunction "K34_K34") (pintype "passive"))
      (node (ref "J3") (pin "K35") (pinfunction "K35_K35") (pintype "passive"))
      (node (ref "J3") (pin "K38") (pinfunction "K38_K38") (pintype "passive"))
      (node (ref "J3") (pin "K39") (pinfunction "K39_K39") (pintype "passive"))
      (node (ref "J3") (pin "K40") (pinfunction "K40_K40") (pintype "passive"))
      (node (ref "J3") (pin "K6") (pinfunction "K06_K6") (pintype "passive"))
      (node (ref "J3") (pin "K7") (pinfunction "K07_K7") (pintype "passive"))
    )
  )
)
